# Display_and_IOs.net
KiCad netlist of a schematic drawn in Altium Designer
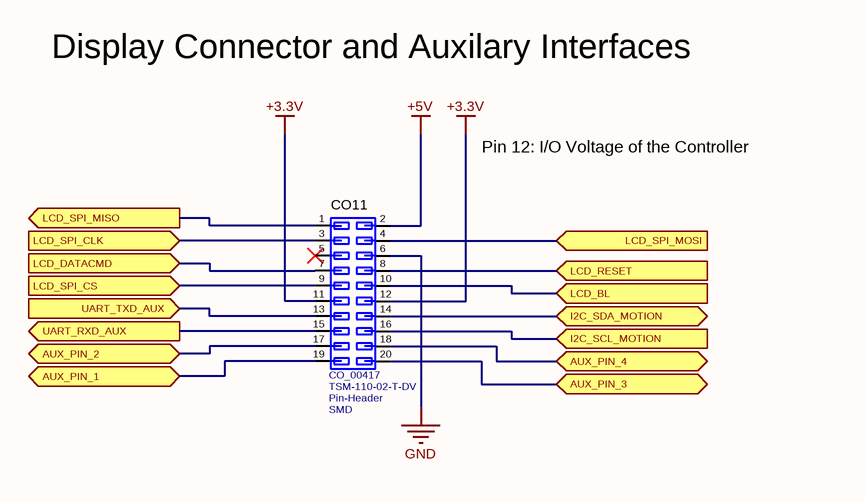
[diagram p0: Display and IOs.SchDoc]

(export (version "E")
  (design (tool "Eeschema 10.0.6"))
  (components
    (comp (ref "CO11")
      (value "header2x10")
      (footprint "CO_00417N")
      (description "SMT .025\" SQ POST HEADER")
      (fields
        (field (name "PART_NUMBER") "CO_00417")
        (field (name "MANUFACTURER_NUMBER") "TSM-110-02-T-DV")
        (field (name "CONNECTOR_TYPE") "Pin-Header")
        (field (name "MOUNTING") "SMD")
        (field (name "POWER") "0W")
        (field (name "CREATOR") "Krenn Markus")
      )
      (libsource (lib "Central Library") (part "header2x10"))
    )
  )
  (nets
    (net (code "1") (name "+3.3V") (class "Default")
      (node (ref "CO11") (pin "11") (pinfunction "PIN11_11") (pintype "passive"))
      (node (ref "CO11") (pin "12") (pinfunction "PIN12_12") (pintype "passive"))
    )
    (net (code "2") (name "+5V") (class "Default")
      (node (ref "CO11") (pin "2") (pinfunction "PIN2_2") (pintype "passive"))
    )
    (net (code "3") (name "/AUX_PIN_1") (class "Default")
      (node (ref "CO11") (pin "19") (pinfunction "PIN19_19") (pintype "passive"))
    )
    (net (code "4") (name "/AUX_PIN_2") (class "Default")
      (node (ref "CO11") (pin "17") (pinfunction "PIN17_17") (pintype "passive"))
    )
    (net (code "5") (name "/AUX_PIN_3") (class "Default")
      (node (ref "CO11") (pin "20") (pinfunction "PIN20_20") (pintype "passive"))
    )
    (net (code "6") (name "/AUX_PIN_4") (class "Default")
      (node (ref "CO11") (pin "18") (pinfunction "PIN18_18") (pintype "passive"))
    )
    (net (code "7") (name "/I2C_SCL_MOTION") (class "Default")
      (node (ref "CO11") (pin "16") (pinfunction "PIN16_16") (pintype "passive"))
    )
    (net (code "8") (name "/I2C_SDA_MOTION") (class "Default")
      (node (ref "CO11") (pin "14") (pinfunction "PIN14_14") (pintype "passive"))
    )
    (net (code "9") (name "/LCD_BL") (class "Default")
      (node (ref "CO11") (pin "10") (pinfunction "PIN10_10") (pintype "passive"))
    )
    (net (code "10") (name "/LCD_DATACMD") (class "Default")
      (node (ref "CO11") (pin "7") (pinfunction "PIN7_7") (pintype "passive"))
    )
    (net (code "11") (name "/LCD_RESET") (class "Default")
      (node (ref "CO11") (pin "8") (pinfunction "PIN8_8") (pintype "passive"))
    )
    (net (code "12") (name "/LCD_SPI_CLK") (class "Default")
      (node (ref "CO11") (pin "3") (pinfunction "PIN3_3") (pintype "passive"))
    )
    (net (code "13") (name "/LCD_SPI_CS") (class "Default")
      (node (ref "CO11") (pin "9") (pinfunction "PIN9_9") (pintype "passive"))
    )
    (net (code "14") (name "/LCD_SPI_MISO") (class "Default")
      (node (ref "CO11") (pin "1") (pinfunction "PIN1_1") (pintype "passive"))
    )
    (net (code "15") (name "/LCD_SPI_MOSI") (class "Default")
      (node (ref "CO11") (pin "4") (pinfunction "PIN4_4") (pintype "passive"))
    )
    (net (code "16") (name "/UART_RXD_AUX") (class "Default")
      (node (ref "CO11") (pin "15") (pinfunction "PIN15_15") (pintype "passive"))
    )
    (net (code "17") (name "/UART_TXD_AUX") (class "Default")
      (node (ref "CO11") (pin "13") (pinfunction "PIN13_13") (pintype "passive"))
    )
    (net (code "18") (name "GND") (class "Default")
      (node (ref "CO11") (pin "6") (pinfunction "PIN6_6") (pintype "passive"))
    )
    (net (code "19") (name "unconnected-(CO11-PIN5-Pad5)") (class "Default")
      (node (ref "CO11") (pin "5") (pinfunction "PIN5_5") (pintype "passive+no_connect"))
    )
  )
)
